# Horn_Board.net
KiCad netlist of a schematic drawn in EAGLE
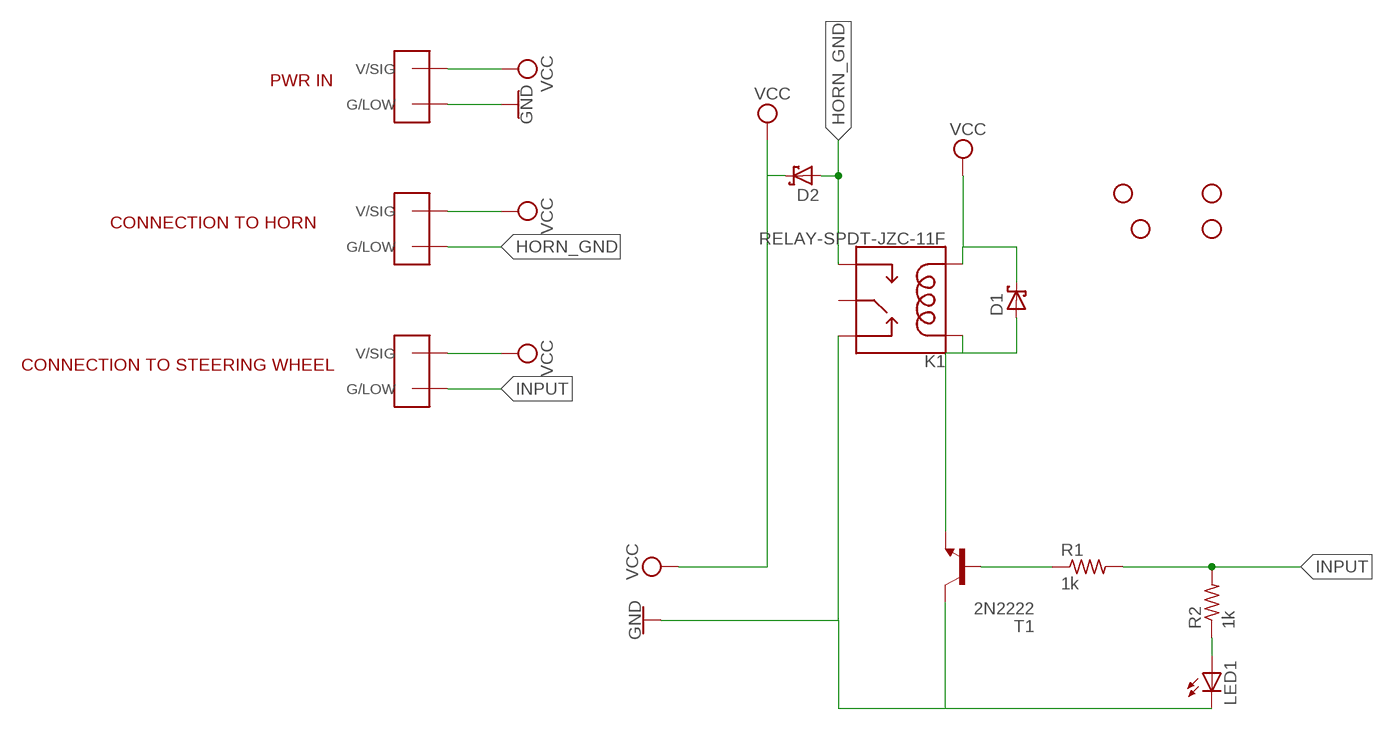
[diagram p0: schematic, sheet 1]

(export (version "E")
  (design (tool "Eeschema 10.0.6"))
  (components
    (comp (ref "D1")
      (value "SCHOTTKY-DIODEAG")
      (footprint "eagle-import:AG")
      (libsource (lib "eagle-import") (part "SCHOTTKY-DIODEAG"))
    )
    (comp (ref "D2")
      (value "SCHOTTKY-DIODEAG")
      (footprint "eagle-import:AG")
      (libsource (lib "eagle-import") (part "SCHOTTKY-DIODEAG"))
    )
    (comp (ref "H1")
      (value "STAND-OFF")
      (footprint "eagle-import:STAND-OFF")
      (libsource (lib "eagle-import") (part "STAND-OFF"))
    )
    (comp (ref "H2")
      (value "STAND-OFF")
      (footprint "eagle-import:STAND-OFF")
      (libsource (lib "eagle-import") (part "STAND-OFF"))
    )
    (comp (ref "H3")
      (value "STAND-OFF")
      (footprint "eagle-import:STAND-OFF")
      (libsource (lib "eagle-import") (part "STAND-OFF"))
    )
    (comp (ref "H4")
      (value "STAND-OFF")
      (footprint "eagle-import:STAND-OFF")
      (libsource (lib "eagle-import") (part "STAND-OFF"))
    )
    (comp (ref "K1")
      (value "RELAY-SPDT-JZC-11F")
      (footprint "eagle-import:RELAY-JZC")
      (libsource (lib "eagle-import") (part "RELAY-SPDT-JZC-11F"))
    )
    (comp (ref "LED1")
      (value "LED")
      (footprint "eagle-import:SMARTLED-TTW")
      (libsource (lib "eagle-import") (part "LED"))
    )
    (comp (ref "R1")
      (value "1k")
      (footprint "eagle-import:0204V")
      (libsource (lib "eagle-import") (part "R-US_0204/2V"))
    )
    (comp (ref "R2")
      (value "1k")
      (footprint "eagle-import:0204V")
      (libsource (lib "eagle-import") (part "R-US_0204/2V"))
    )
    (comp (ref "T1")
      (value "2N2222")
      (footprint "eagle-import:TO92-EBC-OVAL")
      (libsource (lib "eagle-import") (part "2N2222"))
    )
    (comp (ref "U$1")
      (value "TE770966")
      (footprint "eagle-import:2X1-MATE-N-LOCK")
      (libsource (lib "eagle-import") (part "TE770966"))
    )
    (comp (ref "U$2")
      (value "TE770966")
      (footprint "eagle-import:2X1-MATE-N-LOCK")
      (libsource (lib "eagle-import") (part "TE770966"))
    )
    (comp (ref "U$8")
      (value "TE770966")
      (footprint "eagle-import:2X1-MATE-N-LOCK")
      (libsource (lib "eagle-import") (part "TE770966"))
    )
  )
  (nets
    (net (code "1") (name "GND") (class "Default")
      (node (ref "K1") (pin "2") (pinfunction "NC_2") (pintype "bidirectional"))
      (node (ref "LED1") (pin "C@1") (pinfunction "C_C@1") (pintype "passive"))
      (node (ref "T1") (pin "C") (pinfunction "C_C") (pintype "passive"))
      (node (ref "U$8") (pin "CIRCUIT2") (pinfunction "G/LOW_CIRCUIT2") (pintype "bidirectional"))
    )
    (net (code "2") (name "HORN_GND") (class "Default")
      (node (ref "D2") (pin "A") (pinfunction "A_A") (pintype "passive"))
      (node (ref "K1") (pin "3") (pinfunction "NO_3") (pintype "bidirectional"))
      (node (ref "U$1") (pin "CIRCUIT2") (pinfunction "G/LOW_CIRCUIT2") (pintype "bidirectional"))
    )
    (net (code "3") (name "INPUT") (class "Default")
      (node (ref "R1") (pin "2") (pinfunction "2_2") (pintype "passive"))
      (node (ref "R2") (pin "2") (pinfunction "2_2") (pintype "passive"))
      (node (ref "U$2") (pin "CIRCUIT2") (pinfunction "G/LOW_CIRCUIT2") (pintype "bidirectional"))
    )
    (net (code "4") (name "Net-(K1-COIL1)") (class "Default")
      (node (ref "D1") (pin "A") (pinfunction "A_A") (pintype "passive"))
      (node (ref "K1") (pin "5") (pinfunction "COIL1_5") (pintype "bidirectional"))
      (node (ref "T1") (pin "E") (pinfunction "E_E") (pintype "passive"))
    )
    (net (code "5") (name "Net-(LED1-A)") (class "Default")
      (node (ref "LED1") (pin "A@1") (pinfunction "A_A@1") (pintype "passive"))
      (node (ref "R2") (pin "1") (pinfunction "1_1") (pintype "passive"))
    )
    (net (code "6") (name "Net-(R1-Pad1)") (class "Default")
      (node (ref "R1") (pin "1") (pinfunction "1_1") (pintype "passive"))
      (node (ref "T1") (pin "B") (pinfunction "B_B") (pintype "passive"))
    )
    (net (code "7") (name "VCC") (class "Default")
      (node (ref "D1") (pin "C") (pinfunction "C_C") (pintype "passive"))
      (node (ref "D2") (pin "C") (pinfunction "C_C") (pintype "passive"))
      (node (ref "K1") (pin "1") (pinfunction "COIL2_1") (pintype "bidirectional"))
      (node (ref "U$1") (pin "CIRCUIT1") (pinfunction "V/SIG_CIRCUIT1") (pintype "bidirectional"))
      (node (ref "U$2") (pin "CIRCUIT1") (pinfunction "V/SIG_CIRCUIT1") (pintype "bidirectional"))
      (node (ref "U$8") (pin "CIRCUIT1") (pinfunction "V/SIG_CIRCUIT1") (pintype "bidirectional"))
    )
    (net (code "8") (name "unconnected-(K1-MAIN-Pad4)") (class "Default")
      (node (ref "K1") (pin "4") (pinfunction "MAIN_4") (pintype "bidirectional"))
    )
  )
)
